# Led.net
KiCad netlist of a schematic drawn in Altium Designer
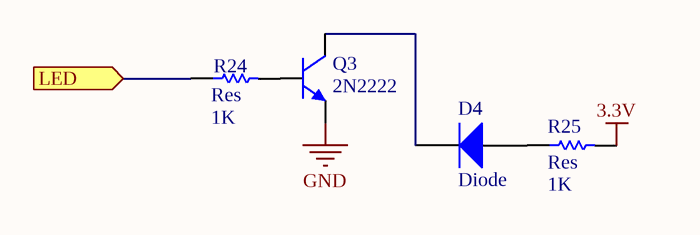
[diagram p0: Led.SchDoc]

(export (version "E")
  (design (tool "Eeschema 10.0.6"))
  (components
    (comp (ref "D4")
      (value "Diode")
      (footprint "2012[0805]")
      (description "1 Amp General Purpose Rectifier")
      (fields (field (name "PUBLISHER") "Altium Limited"))
      (libsource (lib "KN2CLib") (part "Diode"))
    )
    (comp (ref "Q3")
      (value "2N2222")
      (footprint "SOT-23")
      (description "NPN Bipolar Transistor")
      (fields (field (name "PUBLISHER") "Altium Limited"))
      (libsource (lib "KN2CLib") (part "2N2222"))
    )
    (comp (ref "R24")
      (value "Res")
      (footprint "2012[0805]")
      (description "Semiconductor Resistor")
      (fields (field (name "ALTIUM_VALUE") "1K") (field (name "PUBLISHER") "Altium Limited"))
      (libsource (lib "KN2CLib") (part "Res"))
    )
    (comp (ref "R25")
      (value "Res")
      (footprint "2012[0805]")
      (description "Semiconductor Resistor")
      (fields (field (name "ALTIUM_VALUE") "1K") (field (name "PUBLISHER") "Altium Limited"))
      (libsource (lib "KN2CLib") (part "Res"))
    )
  )
  (nets
    (net (code "1") (name "/LED") (class "Default")
      (node (ref "R24") (pin "1") (pinfunction "1_1") (pintype "passive"))
    )
    (net (code "2") (name "3.3V") (class "Default")
      (node (ref "R25") (pin "2") (pinfunction "2_2") (pintype "passive"))
    )
    (net (code "3") (name "GND") (class "Default")
      (node (ref "Q3") (pin "3") (pinfunction "E_3") (pintype "passive"))
    )
    (net (code "4") (name "Net-(D4-A)") (class "Default")
      (node (ref "D4") (pin "1") (pinfunction "A_1") (pintype "passive"))
      (node (ref "R25") (pin "1") (pinfunction "1_1") (pintype "passive"))
    )
    (net (code "5") (name "Net-(D4-K)") (class "Default")
      (node (ref "D4") (pin "2") (pinfunction "K_2") (pintype "passive"))
      (node (ref "Q3") (pin "1") (pinfunction "C_1") (pintype "passive"))
    )
    (net (code "6") (name "Net-(Q3-B)") (class "Default")
      (node (ref "Q3") (pin "2") (pinfunction "B_2") (pintype "passive"))
      (node (ref "R24") (pin "2") (pinfunction "2_2") (pintype "passive"))
    )
  )
)
